# nrf-ethernet.net
KiCad netlist of a schematic drawn in EAGLE
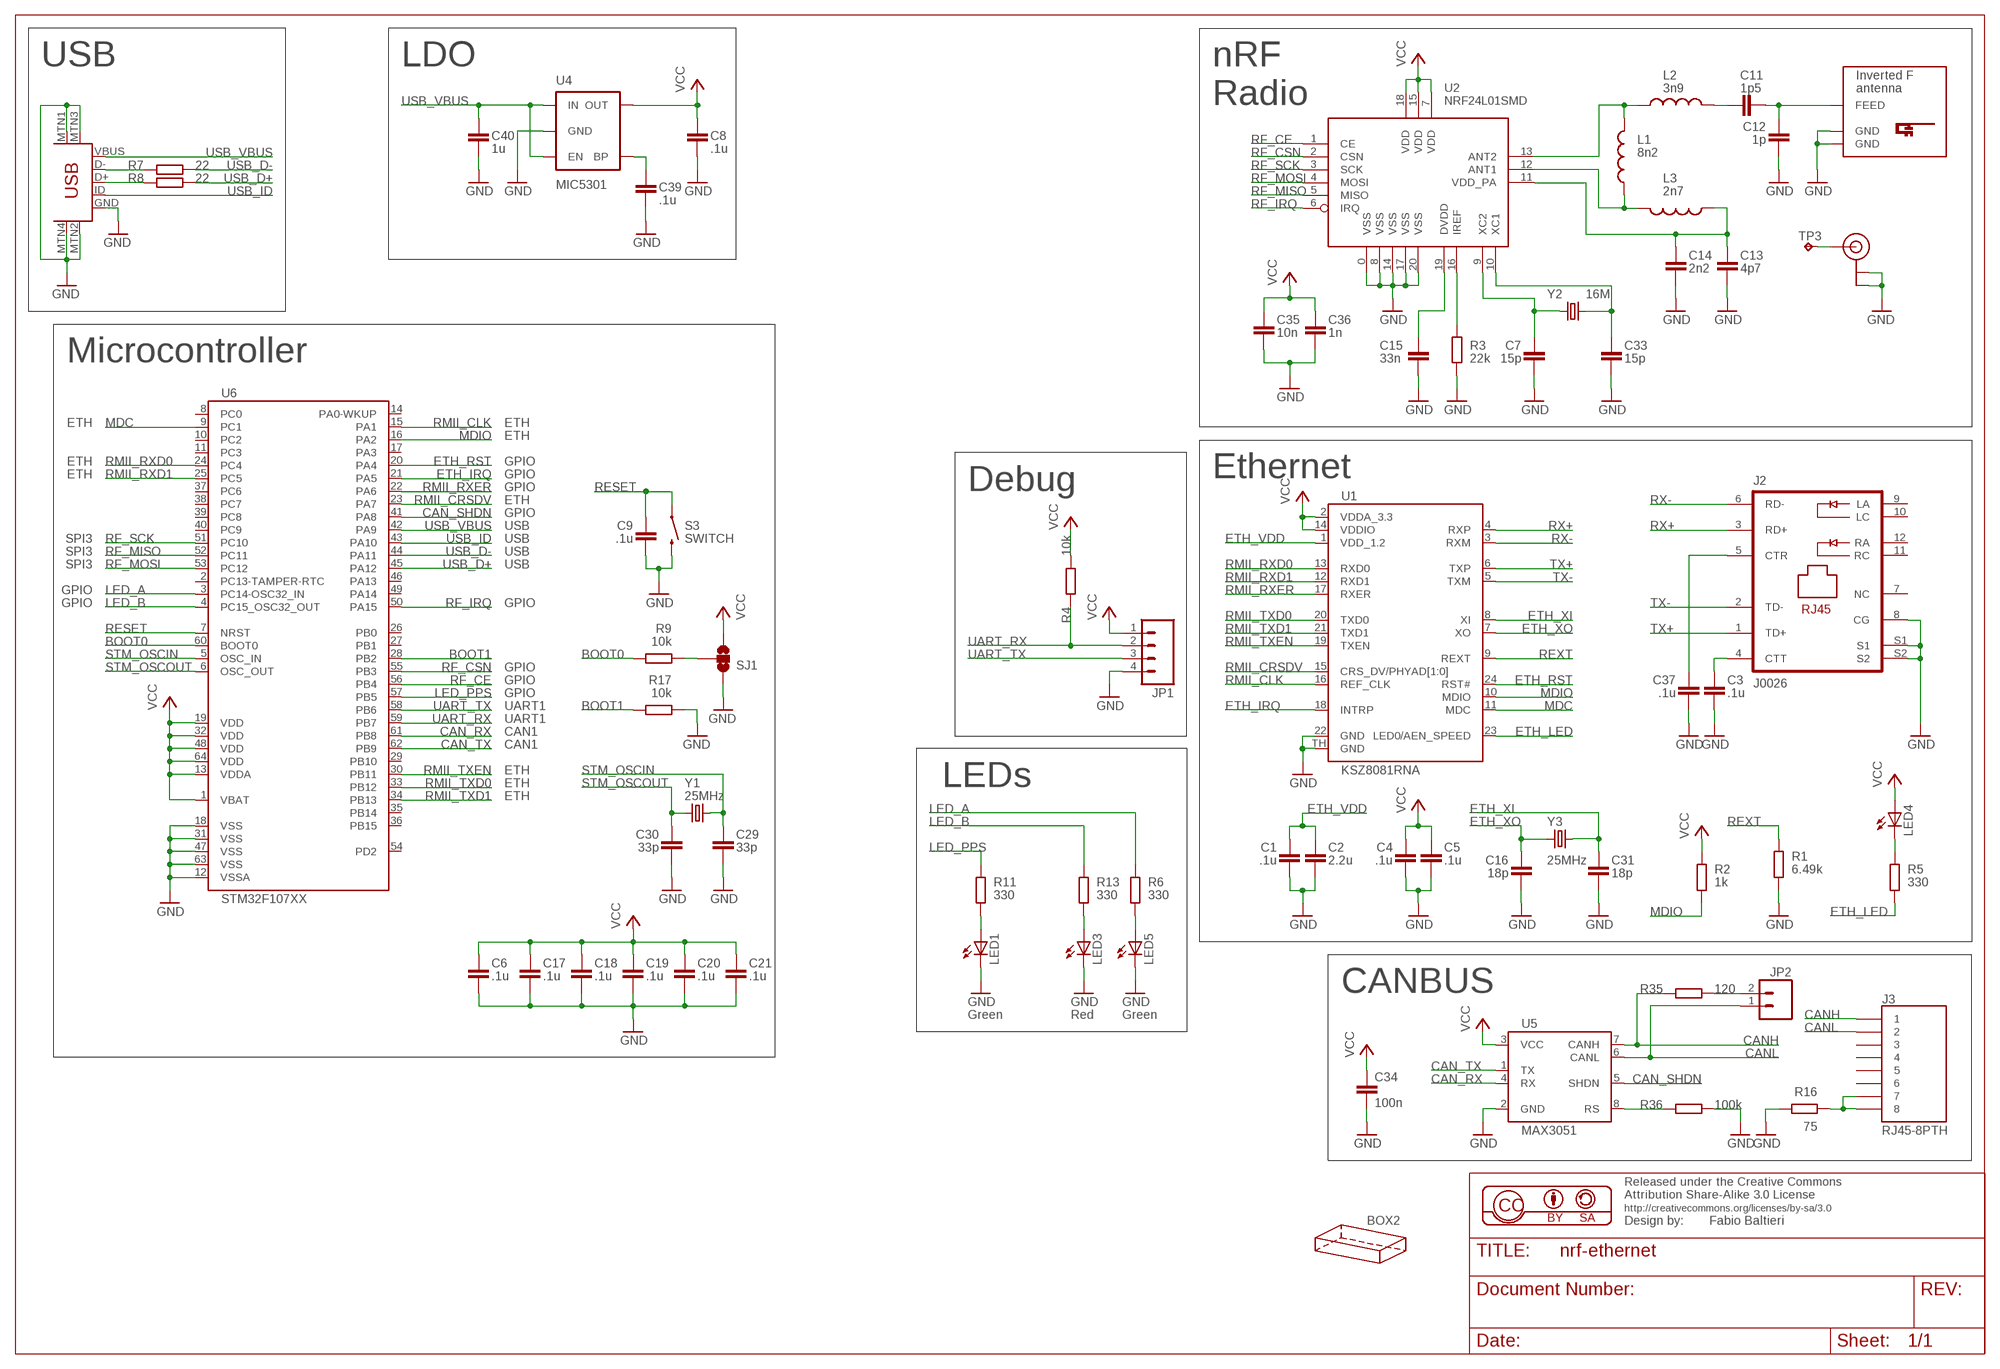
[diagram p0: schematic, sheet 1]

(export (version "E")
  (design (tool "Eeschema 10.0.6"))
  (components
    (comp (ref "BOX2")
      (value "HAMMOND-BOX-K")
      (footprint "eagle-import:1551K")
      (libsource (lib "eagle-import") (part "HAMMOND-BOX-K"))
    )
    (comp (ref "C1")
      (value ".1u")
      (footprint "eagle-import:C0603")
      (libsource (lib "eagle-import") (part "C-EUC0603"))
    )
    (comp (ref "C2")
      (value "2.2u")
      (footprint "eagle-import:C0603")
      (libsource (lib "eagle-import") (part "C-EUC0603"))
    )
    (comp (ref "C3")
      (value ".1u")
      (footprint "eagle-import:C0603")
      (libsource (lib "eagle-import") (part "C-EUC0603"))
    )
    (comp (ref "C4")
      (value ".1u")
      (footprint "eagle-import:C0603")
      (libsource (lib "eagle-import") (part "C-EUC0603"))
    )
    (comp (ref "C5")
      (value ".1u")
      (footprint "eagle-import:C0603")
      (libsource (lib "eagle-import") (part "C-EUC0603"))
    )
    (comp (ref "C6")
      (value ".1u")
      (footprint "eagle-import:C0603")
      (libsource (lib "eagle-import") (part "C-EUC0603"))
    )
    (comp (ref "C7")
      (value "15p")
      (footprint "eagle-import:C0603")
      (libsource (lib "eagle-import") (part "C-EUC0603"))
    )
    (comp (ref "C8")
      (value ".1u")
      (footprint "eagle-import:C0603")
      (libsource (lib "eagle-import") (part "C-EUC0603"))
    )
    (comp (ref "C9")
      (value ".1u")
      (footprint "eagle-import:C0603")
      (libsource (lib "eagle-import") (part "C-EUC0603"))
    )
    (comp (ref "C11")
      (value "1p5")
      (footprint "eagle-import:C0603")
      (libsource (lib "eagle-import") (part "C-EUC0603"))
    )
    (comp (ref "C12")
      (value "1p")
      (footprint "eagle-import:C0603")
      (libsource (lib "eagle-import") (part "C-EUC0603"))
    )
    (comp (ref "C13")
      (value "4p7")
      (footprint "eagle-import:C0603")
      (libsource (lib "eagle-import") (part "C-EUC0603"))
    )
    (comp (ref "C14")
      (value "2n2")
      (footprint "eagle-import:C0603")
      (libsource (lib "eagle-import") (part "C-EUC0603"))
    )
    (comp (ref "C15")
      (value "33n")
      (footprint "eagle-import:C0603")
      (libsource (lib "eagle-import") (part "C-EUC0603"))
    )
    (comp (ref "C16")
      (value "18p")
      (footprint "eagle-import:C0603")
      (libsource (lib "eagle-import") (part "C-EUC0603"))
    )
    (comp (ref "C17")
      (value ".1u")
      (footprint "eagle-import:C0603")
      (libsource (lib "eagle-import") (part "C-EUC0603"))
    )
    (comp (ref "C18")
      (value ".1u")
      (footprint "eagle-import:C0603")
      (libsource (lib "eagle-import") (part "C-EUC0603"))
    )
    (comp (ref "C19")
      (value ".1u")
      (footprint "eagle-import:C0603")
      (libsource (lib "eagle-import") (part "C-EUC0603"))
    )
    (comp (ref "C20")
      (value ".1u")
      (footprint "eagle-import:C0603")
      (libsource (lib "eagle-import") (part "C-EUC0603"))
    )
    (comp (ref "C21")
      (value ".1u")
      (footprint "eagle-import:C0603")
      (libsource (lib "eagle-import") (part "C-EUC0603"))
    )
    (comp (ref "C29")
      (value "33p")
      (footprint "eagle-import:C0603")
      (libsource (lib "eagle-import") (part "C-EUC0603"))
    )
    (comp (ref "C30")
      (value "33p")
      (footprint "eagle-import:C0603")
      (libsource (lib "eagle-import") (part "C-EUC0603"))
    )
    (comp (ref "C31")
      (value "18p")
      (footprint "eagle-import:C0603")
      (libsource (lib "eagle-import") (part "C-EUC0603"))
    )
    (comp (ref "C33")
      (value "15p")
      (footprint "eagle-import:C0603")
      (libsource (lib "eagle-import") (part "C-EUC0603"))
    )
    (comp (ref "C34")
      (value "100n")
      (footprint "eagle-import:C0603")
      (libsource (lib "eagle-import") (part "C-EUC0603"))
    )
    (comp (ref "C35")
      (value "10n")
      (footprint "eagle-import:C0603")
      (libsource (lib "eagle-import") (part "C-EUC0603"))
    )
    (comp (ref "C36")
      (value "1n")
      (footprint "eagle-import:C0603")
      (libsource (lib "eagle-import") (part "C-EUC0603"))
    )
    (comp (ref "C37")
      (value ".1u")
      (footprint "eagle-import:C0603")
      (libsource (lib "eagle-import") (part "C-EUC0603"))
    )
    (comp (ref "C39")
      (value ".1u")
      (footprint "eagle-import:C0603")
      (libsource (lib "eagle-import") (part "C-EUC0603"))
    )
    (comp (ref "C40")
      (value "1u")
      (footprint "eagle-import:C0603")
      (libsource (lib "eagle-import") (part "C-EUC0603"))
    )
    (comp (ref "J2")
      (value "J0026")
      (footprint "eagle-import:PJ-J0")
      (libsource (lib "eagle-import") (part "J0026"))
    )
    (comp (ref "J3")
      (value "RJ45-8PTH")
      (footprint "eagle-import:RJ45-8")
      (libsource (lib "eagle-import") (part "RJ45-8PTH"))
    )
    (comp (ref "JP1")
      (value "M04PTH")
      (footprint "eagle-import:1X04")
      (libsource (lib "eagle-import") (part "M04PTH"))
    )
    (comp (ref "JP2")
      (value "M02PTH")
      (footprint "eagle-import:1X02")
      (libsource (lib "eagle-import") (part "M02PTH"))
    )
    (comp (ref "L1")
      (value "8n2")
      (footprint "eagle-import:0603")
      (libsource (lib "eagle-import") (part "INDUCTOR0603"))
    )
    (comp (ref "L2")
      (value "3n9")
      (footprint "eagle-import:0603")
      (libsource (lib "eagle-import") (part "INDUCTOR0603"))
    )
    (comp (ref "L3")
      (value "2n7")
      (footprint "eagle-import:0603")
      (libsource (lib "eagle-import") (part "INDUCTOR0603"))
    )
    (comp (ref "LED1")
      (value "LEDCHIPLED_0805")
      (footprint "eagle-import:CHIPLED_0805")
      (libsource (lib "eagle-import") (part "LEDCHIPLED_0805"))
    )
    (comp (ref "LED3")
      (value "LEDCHIPLED_0805")
      (footprint "eagle-import:CHIPLED_0805")
      (libsource (lib "eagle-import") (part "LEDCHIPLED_0805"))
    )
    (comp (ref "LED4")
      (value "LEDCHIPLED_0805")
      (footprint "eagle-import:CHIPLED_0805")
      (libsource (lib "eagle-import") (part "LEDCHIPLED_0805"))
    )
    (comp (ref "LED5")
      (value "LEDCHIPLED_0805")
      (footprint "eagle-import:CHIPLED_0805")
      (libsource (lib "eagle-import") (part "LEDCHIPLED_0805"))
    )
    (comp (ref "R1")
      (value "6.49k")
      (footprint "eagle-import:R0603")
      (libsource (lib "eagle-import") (part "R-EU_R0603"))
    )
    (comp (ref "R2")
      (value "1k")
      (footprint "eagle-import:R0603")
      (libsource (lib "eagle-import") (part "R-EU_R0603"))
    )
    (comp (ref "R3")
      (value "22k")
      (footprint "eagle-import:R0603")
      (libsource (lib "eagle-import") (part "R-EU_R0603"))
    )
    (comp (ref "R4")
      (value "10k")
      (footprint "eagle-import:R0603")
      (libsource (lib "eagle-import") (part "R-EU_R0603"))
    )
    (comp (ref "R5")
      (value "330")
      (footprint "eagle-import:R0603")
      (libsource (lib "eagle-import") (part "R-EU_R0603"))
    )
    (comp (ref "R6")
      (value "330")
      (footprint "eagle-import:R0603")
      (libsource (lib "eagle-import") (part "R-EU_R0603"))
    )
    (comp (ref "R7")
      (value "22")
      (footprint "eagle-import:R0603")
      (libsource (lib "eagle-import") (part "R-EU_R0603"))
    )
    (comp (ref "R8")
      (value "22")
      (footprint "eagle-import:R0603")
      (libsource (lib "eagle-import") (part "R-EU_R0603"))
    )
    (comp (ref "R9")
      (value "10k")
      (footprint "eagle-import:R0603")
      (libsource (lib "eagle-import") (part "R-EU_R0603"))
    )
    (comp (ref "R11")
      (value "330")
      (footprint "eagle-import:R0603")
      (libsource (lib "eagle-import") (part "R-EU_R0603"))
    )
    (comp (ref "R13")
      (value "330")
      (footprint "eagle-import:R0603")
      (libsource (lib "eagle-import") (part "R-EU_R0603"))
    )
    (comp (ref "R16")
      (value "75")
      (footprint "eagle-import:R0805")
      (libsource (lib "eagle-import") (part "R-EU_R0805"))
    )
    (comp (ref "R17")
      (value "10k")
      (footprint "eagle-import:R0603")
      (libsource (lib "eagle-import") (part "R-EU_R0603"))
    )
    (comp (ref "R35")
      (value "120")
      (footprint "eagle-import:R0805")
      (libsource (lib "eagle-import") (part "R-EU_R0805"))
    )
    (comp (ref "R36")
      (value "100k")
      (footprint "eagle-import:R0603")
      (libsource (lib "eagle-import") (part "R-EU_R0603"))
    )
    (comp (ref "S3")
      (value "SWITCH")
      (footprint "eagle-import:TACTILE_SWITCH_SMD")
      (libsource (lib "eagle-import") (part "SWITCH-MOMENTARY-2SMD"))
    )
    (comp (ref "SJ1")
      (value "SOLDERJUMPER_2WAYS")
      (footprint "eagle-import:SJ_3")
      (libsource (lib "eagle-import") (part "SOLDERJUMPER_2WAYS"))
    )
    (comp (ref "TP3")
      (value "TPTP08SQ")
      (footprint "eagle-import:TP08SQ")
      (libsource (lib "eagle-import") (part "TPTP08SQ"))
    )
    (comp (ref "U$4")
      (value "USB-MINIB-5PIN")
      (footprint "eagle-import:USB-MINIB")
      (libsource (lib "eagle-import") (part "USB-MINIB-5PIN"))
    )
    (comp (ref "U$5")
      (value "INVERTED_F_ANTENNA-2")
      (footprint "eagle-import:DN007-2")
      (libsource (lib "eagle-import") (part "INVERTED_F_ANTENNA-2"))
    )
    (comp (ref "U$6")
      (value "U.FL")
      (footprint "eagle-import:U.FL")
      (libsource (lib "eagle-import") (part "U.FL"))
    )
    (comp (ref "U1")
      (value "KSZ8081RNA")
      (footprint "eagle-import:QFN24")
      (libsource (lib "eagle-import") (part "KSZ8081"))
    )
    (comp (ref "U2")
      (value "NRF24L01SMD")
      (footprint "eagle-import:QFN20")
      (libsource (lib "eagle-import") (part "NRF24L01SMD"))
    )
    (comp (ref "U4")
      (value "MIC5301")
      (footprint "eagle-import:SOT23-5")
      (libsource (lib "eagle-import") (part "V_REG_LDOSMD"))
    )
    (comp (ref "U5")
      (value "MAX3051")
      (footprint "eagle-import:SO08")
      (libsource (lib "eagle-import") (part "MAX3051"))
    )
    (comp (ref "U6")
      (value "STM32F107XX")
      (footprint "eagle-import:LQFP64")
      (libsource (lib "eagle-import") (part "STM32F107XX"))
    )
    (comp (ref "Y1")
      (value "25MHz")
      (footprint "eagle-import:CRYSTAL-SMD-5X3")
      (libsource (lib "eagle-import") (part "CRYSTAL5X3"))
    )
    (comp (ref "Y2")
      (value "16M")
      (footprint "eagle-import:CRYSTAL-SMD-5X3")
      (libsource (lib "eagle-import") (part "CRYSTAL5X3"))
    )
    (comp (ref "Y3")
      (value "25MHz")
      (footprint "eagle-import:CRYSTAL-SMD-5X3")
      (libsource (lib "eagle-import") (part "CRYSTAL5X3"))
    )
  )
  (nets
    (net (code "1") (name "/BOOT0") (class "Default")
      (node (ref "R9") (pin "2") (pinfunction "2_2") (pintype "passive"))
      (node (ref "U6") (pin "60") (pinfunction "BOOT0_60") (pintype "bidirectional"))
    )
    (net (code "2") (name "/BOOT1") (class "Default")
      (node (ref "R17") (pin "2") (pinfunction "2_2") (pintype "passive"))
      (node (ref "U6") (pin "28") (pinfunction "PB2_28") (pintype "bidirectional"))
    )
    (net (code "3") (name "/CANH") (class "Default")
      (node (ref "J3") (pin "1") (pinfunction "1_1") (pintype "bidirectional"))
      (node (ref "R35") (pin "1") (pinfunction "1_1") (pintype "passive"))
      (node (ref "U5") (pin "7") (pinfunction "CANH_7") (pintype "bidirectional"))
    )
    (net (code "4") (name "/CANL") (class "Default")
      (node (ref "J3") (pin "2") (pinfunction "2_2") (pintype "bidirectional"))
      (node (ref "JP2") (pin "1") (pinfunction "1_1") (pintype "passive"))
      (node (ref "U5") (pin "6") (pinfunction "CANL_6") (pintype "bidirectional"))
    )
    (net (code "5") (name "/CAN_RX") (class "Default")
      (node (ref "U5") (pin "4") (pinfunction "RX_4") (pintype "bidirectional"))
      (node (ref "U6") (pin "61") (pinfunction "PB8_61") (pintype "bidirectional"))
    )
    (net (code "6") (name "/CAN_SHDN") (class "Default")
      (node (ref "U5") (pin "5") (pinfunction "SHDN_5") (pintype "bidirectional"))
      (node (ref "U6") (pin "41") (pinfunction "PA8_41") (pintype "bidirectional"))
    )
    (net (code "7") (name "/CAN_TX") (class "Default")
      (node (ref "U5") (pin "1") (pinfunction "TX_1") (pintype "bidirectional"))
      (node (ref "U6") (pin "62") (pinfunction "PB9_62") (pintype "bidirectional"))
    )
    (net (code "8") (name "/ETH_IRQ") (class "Default")
      (node (ref "U1") (pin "18") (pinfunction "INTRP_18") (pintype "bidirectional"))
      (node (ref "U6") (pin "21") (pinfunction "PA5_21") (pintype "bidirectional"))
    )
    (net (code "9") (name "/ETH_LED") (class "Default")
      (node (ref "R5") (pin "1") (pinfunction "1_1") (pintype "passive"))
      (node (ref "U1") (pin "23") (pinfunction "LED0/AEN_SPEED_23") (pintype "bidirectional"))
    )
    (net (code "10") (name "/ETH_RST") (class "Default")
      (node (ref "U1") (pin "24") (pinfunction "RST#_24") (pintype "bidirectional"))
      (node (ref "U6") (pin "20") (pinfunction "PA4_20") (pintype "bidirectional"))
    )
    (net (code "11") (name "/ETH_VDD") (class "Default")
      (node (ref "C1") (pin "1") (pinfunction "1_1") (pintype "passive"))
      (node (ref "C2") (pin "1") (pinfunction "1_1") (pintype "passive"))
      (node (ref "U1") (pin "1") (pinfunction "VDD_1.2_1") (pintype "bidirectional"))
    )
    (net (code "12") (name "/ETH_XI") (class "Default")
      (node (ref "C31") (pin "1") (pinfunction "1_1") (pintype "passive"))
      (node (ref "U1") (pin "8") (pinfunction "XI_8") (pintype "bidirectional"))
      (node (ref "Y3") (pin "3") (pinfunction "2_3") (pintype "passive"))
    )
    (net (code "13") (name "/ETH_XO") (class "Default")
      (node (ref "C16") (pin "1") (pinfunction "1_1") (pintype "passive"))
      (node (ref "U1") (pin "7") (pinfunction "XO_7") (pintype "bidirectional"))
      (node (ref "Y3") (pin "1") (pinfunction "1_1") (pintype "passive"))
    )
    (net (code "14") (name "/LED_A") (class "Default")
      (node (ref "R6") (pin "2") (pinfunction "2_2") (pintype "passive"))
      (node (ref "U6") (pin "3") (pinfunction "PC14-OSC32_IN_3") (pintype "bidirectional"))
    )
    (net (code "15") (name "/LED_B") (class "Default")
      (node (ref "R13") (pin "2") (pinfunction "2_2") (pintype "passive"))
      (node (ref "U6") (pin "4") (pinfunction "PC15_OSC32_OUT_4") (pintype "bidirectional"))
    )
    (net (code "16") (name "/LED_PPS") (class "Default")
      (node (ref "R11") (pin "2") (pinfunction "2_2") (pintype "passive"))
      (node (ref "U6") (pin "57") (pinfunction "PB5_57") (pintype "bidirectional"))
    )
    (net (code "17") (name "/MDC") (class "Default")
      (node (ref "U1") (pin "11") (pinfunction "MDC_11") (pintype "bidirectional"))
      (node (ref "U6") (pin "9") (pinfunction "PC1_9") (pintype "bidirectional"))
    )
    (net (code "18") (name "/MDIO") (class "Default")
      (node (ref "R2") (pin "1") (pinfunction "1_1") (pintype "passive"))
      (node (ref "U1") (pin "10") (pinfunction "MDIO_10") (pintype "bidirectional"))
      (node (ref "U6") (pin "16") (pinfunction "PA2_16") (pintype "bidirectional"))
    )
    (net (code "19") (name "/RESET") (class "Default")
      (node (ref "C9") (pin "1") (pinfunction "1_1") (pintype "passive"))
      (node (ref "S3") (pin "1") (pinfunction "1_1") (pintype "passive"))
      (node (ref "U6") (pin "7") (pinfunction "NRST_7") (pintype "bidirectional"))
    )
    (net (code "20") (name "/REXT") (class "Default")
      (node (ref "R1") (pin "2") (pinfunction "2_2") (pintype "passive"))
      (node (ref "U1") (pin "9") (pinfunction "REXT_9") (pintype "bidirectional"))
    )
    (net (code "21") (name "/RF_CE") (class "Default")
      (node (ref "U2") (pin "1") (pinfunction "CE_1") (pintype "input"))
      (node (ref "U6") (pin "56") (pinfunction "PB4_56") (pintype "bidirectional"))
    )
    (net (code "22") (name "/RF_CSN") (class "Default")
      (node (ref "U2") (pin "2") (pinfunction "CSN_2") (pintype "input"))
      (node (ref "U6") (pin "55") (pinfunction "PB3_55") (pintype "bidirectional"))
    )
    (net (code "23") (name "/RF_IRQ") (class "Default")
      (node (ref "U2") (pin "6") (pinfunction "IRQ_6") (pintype "output"))
      (node (ref "U6") (pin "50") (pinfunction "PA15_50") (pintype "bidirectional"))
    )
    (net (code "24") (name "/RF_MISO") (class "Default")
      (node (ref "U2") (pin "5") (pinfunction "MISO_5") (pintype "output"))
      (node (ref "U6") (pin "52") (pinfunction "PC11_52") (pintype "bidirectional"))
    )
    (net (code "25") (name "/RF_MOSI") (class "Default")
      (node (ref "U2") (pin "4") (pinfunction "MOSI_4") (pintype "input"))
      (node (ref "U6") (pin "53") (pinfunction "PC12_53") (pintype "bidirectional"))
    )
    (net (code "26") (name "/RF_SCK") (class "Default")
      (node (ref "U2") (pin "3") (pinfunction "SCK_3") (pintype "input"))
      (node (ref "U6") (pin "51") (pinfunction "PC10_51") (pintype "bidirectional"))
    )
    (net (code "27") (name "/RMII_CLK") (class "Default")
      (node (ref "U1") (pin "16") (pinfunction "REF_CLK_16") (pintype "bidirectional"))
      (node (ref "U6") (pin "15") (pinfunction "PA1_15") (pintype "bidirectional"))
    )
    (net (code "28") (name "/RMII_CRSDV") (class "Default")
      (node (ref "U1") (pin "15") (pinfunction "CRS_DV/PHYAD[1:0]_15") (pintype "bidirectional"))
      (node (ref "U6") (pin "23") (pinfunction "PA7_23") (pintype "bidirectional"))
    )
    (net (code "29") (name "/RMII_RXD0") (class "Default")
      (node (ref "U1") (pin "13") (pinfunction "RXD0_13") (pintype "bidirectional"))
      (node (ref "U6") (pin "24") (pinfunction "PC4_24") (pintype "bidirectional"))
    )
    (net (code "30") (name "/RMII_RXD1") (class "Default")
      (node (ref "U1") (pin "12") (pinfunction "RXD1_12") (pintype "bidirectional"))
      (node (ref "U6") (pin "25") (pinfunction "PC5_25") (pintype "bidirectional"))
    )
    (net (code "31") (name "/RMII_RXER") (class "Default")
      (node (ref "U1") (pin "17") (pinfunction "RXER_17") (pintype "bidirectional"))
      (node (ref "U6") (pin "22") (pinfunction "PA6_22") (pintype "bidirectional"))
    )
    (net (code "32") (name "/RMII_TXD0") (class "Default")
      (node (ref "U1") (pin "20") (pinfunction "TXD0_20") (pintype "bidirectional"))
      (node (ref "U6") (pin "33") (pinfunction "PB12_33") (pintype "bidirectional"))
    )
    (net (code "33") (name "/RMII_TXD1") (class "Default")
      (node (ref "U1") (pin "21") (pinfunction "TXD1_21") (pintype "bidirectional"))
      (node (ref "U6") (pin "34") (pinfunction "PB13_34") (pintype "bidirectional"))
    )
    (net (code "34") (name "/RMII_TXEN") (class "Default")
      (node (ref "U1") (pin "19") (pinfunction "TXEN_19") (pintype "bidirectional"))
      (node (ref "U6") (pin "30") (pinfunction "PB11_30") (pintype "bidirectional"))
    )
    (net (code "35") (name "/RX+") (class "Default")
      (node (ref "J2") (pin "3") (pinfunction "RD+_3") (pintype "bidirectional"))
      (node (ref "U1") (pin "4") (pinfunction "RXP_4") (pintype "bidirectional"))
    )
    (net (code "36") (name "/RX-") (class "Default")
      (node (ref "J2") (pin "6") (pinfunction "RD-_6") (pintype "bidirectional"))
      (node (ref "U1") (pin "3") (pinfunction "RXM_3") (pintype "bidirectional"))
    )
    (net (code "37") (name "/STM_OSCIN") (class "Default")
      (node (ref "C29") (pin "1") (pinfunction "1_1") (pintype "passive"))
      (node (ref "U6") (pin "5") (pinfunction "OSC_IN_5") (pintype "bidirectional"))
      (node (ref "Y1") (pin "3") (pinfunction "2_3") (pintype "passive"))
    )
    (net (code "38") (name "/STM_OSCOUT") (class "Default")
      (node (ref "C30") (pin "1") (pinfunction "1_1") (pintype "passive"))
      (node (ref "U6") (pin "6") (pinfunction "OSC_OUT_6") (pintype "bidirectional"))
      (node (ref "Y1") (pin "1") (pinfunction "1_1") (pintype "passive"))
    )
    (net (code "39") (name "/TX+") (class "Default")
      (node (ref "J2") (pin "1") (pinfunction "TD+_1") (pintype "bidirectional"))
      (node (ref "U1") (pin "6") (pinfunction "TXP_6") (pintype "bidirectional"))
    )
    (net (code "40") (name "/TX-") (class "Default")
      (node (ref "J2") (pin "2") (pinfunction "TD-_2") (pintype "bidirectional"))
      (node (ref "U1") (pin "5") (pinfunction "TXM_5") (pintype "bidirectional"))
    )
    (net (code "41") (name "/UART_RX") (class "Default")
      (node (ref "JP1") (pin "2") (pinfunction "2_2") (pintype "passive"))
      (node (ref "R4") (pin "1") (pinfunction "1_1") (pintype "passive"))
      (node (ref "U6") (pin "59") (pinfunction "PB7_59") (pintype "bidirectional"))
    )
    (net (code "42") (name "/UART_TX") (class "Default")
      (node (ref "JP1") (pin "3") (pinfunction "3_3") (pintype "passive"))
      (node (ref "U6") (pin "58") (pinfunction "PB6_58") (pintype "bidirectional"))
    )
    (net (code "43") (name "/USB_D+") (class "Default")
      (node (ref "R8") (pin "2") (pinfunction "2_2") (pintype "passive"))
      (node (ref "U6") (pin "45") (pinfunction "PA12_45") (pintype "bidirectional"))
    )
    (net (code "44") (name "/USB_D-") (class "Default")
      (node (ref "R7") (pin "2") (pinfunction "2_2") (pintype "passive"))
      (node (ref "U6") (pin "44") (pinfunction "PA11_44") (pintype "bidirectional"))
    )
    (net (code "45") (name "/USB_ID") (class "Default")
      (node (ref "U$4") (pin "ID") (pinfunction "ID_ID") (pintype "bidirectional"))
      (node (ref "U6") (pin "43") (pinfunction "PA10_43") (pintype "bidirectional"))
    )
    (net (code "46") (name "/USB_VBUS") (class "Default")
      (node (ref "C40") (pin "1") (pinfunction "1_1") (pintype "passive"))
      (node (ref "U$4") (pin "VBUS") (pinfunction "VBUS_VBUS") (pintype "bidirectional"))
      (node (ref "U4") (pin "1") (pinfunction "IN_1") (pintype "input"))
      (node (ref "U4") (pin "3") (pinfunction "EN_3") (pintype "input"))
      (node (ref "U6") (pin "42") (pinfunction "PA9_42") (pintype "bidirectional"))
    )
    (net (code "47") (name "GND") (class "Default")
      (node (ref "C1") (pin "2") (pinfunction "2_2") (pintype "passive"))
      (node (ref "C12") (pin "2") (pinfunction "2_2") (pintype "passive"))
      (node (ref "C13") (pin "2") (pinfunction "2_2") (pintype "passive"))
      (node (ref "C14") (pin "2") (pinfunction "2_2") (pintype "passive"))
      (node (ref "C15") (pin "2") (pinfunction "2_2") (pintype "passive"))
      (node (ref "C16") (pin "2") (pinfunction "2_2") (pintype "passive"))
      (node (ref "C17") (pin "2") (pinfunction "2_2") (pintype "passive"))
      (node (ref "C18") (pin "2") (pinfunction "2_2") (pintype "passive"))
      (node (ref "C19") (pin "2") (pinfunction "2_2") (pintype "passive"))
      (node (ref "C2") (pin "2") (pinfunction "2_2") (pintype "passive"))
      (node (ref "C20") (pin "2") (pinfunction "2_2") (pintype "passive"))
      (node (ref "C21") (pin "2") (pinfunction "2_2") (pintype "passive"))
      (node (ref "C29") (pin "2") (pinfunction "2_2") (pintype "passive"))
      (node (ref "C3") (pin "2") (pinfunction "2_2") (pintype "passive"))
      (node (ref "C30") (pin "2") (pinfunction "2_2") (pintype "passive"))
      (node (ref "C31") (pin "2") (pinfunction "2_2") (pintype "passive"))
      (node (ref "C33") (pin "2") (pinfunction "2_2") (pintype "passive"))
      (node (ref "C34") (pin "2") (pinfunction "2_2") (pintype "passive"))
      (node (ref "C35") (pin "2") (pinfunction "2_2") (pintype "passive"))
      (node (ref "C36") (pin "2") (pinfunction "2_2") (pintype "passive"))
      (node (ref "C37") (pin "2") (pinfunction "2_2") (pintype "passive"))
      (node (ref "C39") (pin "2") (pinfunction "2_2") (pintype "passive"))
      (node (ref "C4") (pin "2") (pinfunction "2_2") (pintype "passive"))
      (node (ref "C40") (pin "2") (pinfunction "2_2") (pintype "passive"))
      (node (ref "C5") (pin "2") (pinfunction "2_2") (pintype "passive"))
      (node (ref "C6") (pin "2") (pinfunction "2_2") (pintype "passive"))
      (node (ref "C7") (pin "2") (pinfunction "2_2") (pintype "passive"))
      (node (ref "C8") (pin "2") (pinfunction "2_2") (pintype "passive"))
      (node (ref "C9") (pin "2") (pinfunction "2_2") (pintype "passive"))
      (node (ref "J2") (pin "8") (pinfunction "CG_8") (pintype "passive"))
      (node (ref "J2") (pin "S1") (pinfunction "S1_S1") (pintype "passive"))
      (node (ref "J2") (pin "S2") (pinfunction "S2_S2") (pintype "passive"))
      (node (ref "JP1") (pin "4") (pinfunction "4_4") (pintype "passive"))
      (node (ref "LED1") (pin "C") (pinfunction "C_C") (pintype "passive"))
      (node (ref "LED3") (pin "C") (pinfunction "C_C") (pintype "passive"))
      (node (ref "LED5") (pin "C") (pinfunction "C_C") (pintype "passive"))
      (node (ref "R1") (pin "1") (pinfunction "1_1") (pintype "passive"))
      (node (ref "R16") (pin "1") (pinfunction "1_1") (pintype "passive"))
      (node (ref "R17") (pin "1") (pinfunction "1_1") (pintype "passive"))
      (node (ref "R3") (pin "2") (pinfunction "2_2") (pintype "passive"))
      (node (ref "R36") (pin "2") (pinfunction "2_2") (pintype "passive"))
      (node (ref "S3") (pin "3") (pinfunction "2_3") (pintype "passive"))
      (node (ref "SJ1") (pin "1") (pinfunction "1_1") (pintype "passive"))
      (node (ref "U$4") (pin "GND") (pinfunction "GND_GND") (pintype "bidirectional"))
      (node (ref "U$4") (pin "MTN1") (pinfunction "MTN2_MTN1") (pintype "bidirectional"))
      (node (ref "U$4") (pin "MTN2") (pinfunction "MTN3_MTN2") (pintype "bidirectional"))
      (node (ref "U$4") (pin "MTN3") (pinfunction "MTN1_MTN3") (pintype "bidirectional"))
      (node (ref "U$4") (pin "MTN4") (pinfunction "MTN4_MTN4") (pintype "bidirectional"))
      (node (ref "U$5") (pin "GND") (pinfunction "GND_GND") (pintype "bidirectional"))
      (node (ref "U$5") (pin "GND@1") (pinfunction "GND_GND@1") (pintype "bidirectional"))
      (node (ref "U$6") (pin "P$1") (pinfunction "GND_P$1") (pintype "bidirectional"))
      (node (ref "U$6") (pin "P$2") (pinfunction "GND_P$2") (pintype "bidirectional"))
      (node (ref "U1") (pin "22") (pinfunction "GND_22") (pintype "bidirectional"))
      (node (ref "U1") (pin "TH") (pinfunction "GND_TH") (pintype "bidirectional"))
      (node (ref "U2") (pin "0") (pinfunction "VSS_0") (pintype "power_in"))
      (node (ref "U2") (pin "14") (pinfunction "VSS_14") (pintype "power_in"))
      (node (ref "U2") (pin "17") (pinfunction "VSS_17") (pintype "power_in"))
      (node (ref "U2") (pin "20") (pinfunction "VSS_20") (pintype "power_in"))
      (node (ref "U2") (pin "8") (pinfunction "VSS_8") (pintype "power_in"))
      (node (ref "U4") (pin "2") (pinfunction "GND_2") (pintype "input"))
      (node (ref "U5") (pin "2") (pinfunction "GND_2") (pintype "bidirectional"))
      (node (ref "U6") (pin "12") (pinfunction "VSSA_12") (pintype "bidirectional"))
      (node (ref "U6") (pin "18") (pinfunction "VSS_18") (pintype "bidirectional"))
      (node (ref "U6") (pin "31") (pinfunction "VSS_31") (pintype "bidirectional"))
      (node (ref "U6") (pin "47") (pinfunction "VSS_47") (pintype "bidirectional"))
      (node (ref "U6") (pin "63") (pinfunction "VSS_63") (pintype "bidirectional"))
    )
    (net (code "48") (name "Net-(C11-Pad1)") (class "Default")
      (node (ref "C11") (pin "1") (pinfunction "1_1") (pintype "passive"))
      (node (ref "L2") (pin "2") (pinfunction "2_2") (pintype "passive"))
    )
    (net (code "49") (name "Net-(C11-Pad2)") (class "Default")
      (node (ref "C11") (pin "2") (pinfunction "2_2") (pintype "passive"))
      (node (ref "C12") (pin "1") (pinfunction "1_1") (pintype "passive"))
      (node (ref "U$5") (pin "FEED") (pinfunction "FEED_FEED") (pintype "bidirectional"))
    )
    (net (code "50") (name "Net-(J2-CTR)") (class "Default")
      (node (ref "C37") (pin "1") (pinfunction "1_1") (pintype "passive"))
      (node (ref "J2") (pin "5") (pinfunction "CTR_5") (pintype "bidirectional"))
    )
    (net (code "51") (name "Net-(J2-CTT)") (class "Default")
      (node (ref "C3") (pin "1") (pinfunction "1_1") (pintype "passive"))
      (node (ref "J2") (pin "4") (pinfunction "CTT_4") (pintype "bidirectional"))
    )
    (net (code "52") (name "Net-(J3-Pad7)") (class "Default")
      (node (ref "J3") (pin "7") (pinfunction "7_7") (pintype "bidirectional"))
      (node (ref "J3") (pin "8") (pinfunction "8_8") (pintype "bidirectional"))
      (node (ref "R16") (pin "2") (pinfunction "2_2") (pintype "passive"))
    )
    (net (code "53") (name "Net-(JP2-Pad2)") (class "Default")
      (node (ref "JP2") (pin "2") (pinfunction "2_2") (pintype "passive"))
      (node (ref "R35") (pin "2") (pinfunction "2_2") (pintype "passive"))
    )
    (net (code "54") (name "Net-(LED1-PadA)") (class "Default")
      (node (ref "LED1") (pin "A") (pinfunction "A_A") (pintype "passive"))
      (node (ref "R11") (pin "1") (pinfunction "1_1") (pintype "passive"))
    )
    (net (code "55") (name "Net-(LED3-PadA)") (class "Default")
      (node (ref "LED3") (pin "A") (pinfunction "A_A") (pintype "passive"))
      (node (ref "R13") (pin "1") (pinfunction "1_1") (pintype "passive"))
    )
    (net (code "56") (name "Net-(LED4-PadC)") (class "Default")
      (node (ref "LED4") (pin "C") (pinfunction "C_C") (pintype "passive"))
      (node (ref "R5") (pin "2") (pinfunction "2_2") (pintype "passive"))
    )
    (net (code "57") (name "Net-(LED5-PadA)") (class "Default")
      (node (ref "LED5") (pin "A") (pinfunction "A_A") (pintype "passive"))
      (node (ref "R6") (pin "1") (pinfunction "1_1") (pintype "passive"))
    )
    (net (code "58") (name "Net-(R7-Pad1)") (class "Default")
      (node (ref "R7") (pin "1") (pinfunction "1_1") (pintype "passive"))
      (node (ref "U$4") (pin "D-") (pinfunction "D-_D-") (pintype "bidirectional"))
    )
    (net (code "59") (name "Net-(R8-Pad1)") (class "Default")
      (node (ref "R8") (pin "1") (pinfunction "1_1") (pintype "passive"))
      (node (ref "U$4") (pin "D+") (pinfunction "D+_D+") (pintype "bidirectional"))
    )
    (net (code "60") (name "Net-(R9-Pad1)") (class "Default")
      (node (ref "R9") (pin "1") (pinfunction "1_1") (pintype "passive"))
      (node (ref "SJ1") (pin "2") (pinfunction "2_2") (pintype "passive"))
    )
    (net (code "61") (name "Net-(U$6-SIGNAL)") (class "Default")
      (node (ref "TP3") (pin "TP") (pinfunction "TP_TP") (pintype "input"))
      (node (ref "U$6") (pin "P$3") (pinfunction "SIGNAL_P$3") (pintype "bidirectional"))
    )
    (net (code "62") (name "Net-(U2-ANT1)") (class "Default")
      (node (ref "L1") (pin "2") (pinfunction "2_2") (pintype "passive"))
      (node (ref "L3") (pin "2") (pinfunction "2_2") (pintype "passive"))
      (node (ref "U2") (pin "12") (pinfunction "ANT1_12") (pintype "output"))
    )
    (net (code "63") (name "Net-(U2-ANT2)") (class "Default")
      (node (ref "L1") (pin "1") (pinfunction "1_1") (pintype "passive"))
      (node (ref "L2") (pin "1") (pinfunction "1_1") (pintype "passive"))
      (node (ref "U2") (pin "13") (pinfunction "ANT2_13") (pintype "output"))
    )
    (net (code "64") (name "Net-(U2-DVDD)") (class "Default")
      (node (ref "C15") (pin "1") (pinfunction "1_1") (pintype "passive"))
      (node (ref "U2") (pin "19") (pinfunction "DVDD_19") (pintype "power_in"))
    )
    (net (code "65") (name "Net-(U2-IREF)") (class "Default")
      (node (ref "R3") (pin "1") (pinfunction "1_1") (pintype "passive"))
      (node (ref "U2") (pin "16") (pinfunction "IREF_16") (pintype "input"))
    )
    (net (code "66") (name "Net-(U2-VDD_PA)") (class "Default")
      (node (ref "C13") (pin "1") (pinfunction "1_1") (pintype "passive"))
      (node (ref "C14") (pin "1") (pinfunction "1_1") (pintype "passive"))
      (node (ref "L3") (pin "1") (pinfunction "1_1") (pintype "passive"))
      (node (ref "U2") (pin "11") (pinfunction "VDD_PA_11") (pintype "power_in"))
    )
    (net (code "67") (name "Net-(U2-XC1)") (class "Default")
      (node (ref "C33") (pin "1") (pinfunction "1_1") (pintype "passive"))
      (node (ref "U2") (pin "10") (pinfunction "XC1_10") (pintype "input"))
      (node (ref "Y2") (pin "3") (pinfunction "2_3") (pintype "passive"))
    )
    (net (code "68") (name "Net-(U2-XC2)") (class "Default")
      (node (ref "C7") (pin "1") (pinfunction "1_1") (pintype "passive"))
      (node (ref "U2") (pin "9") (pinfunction "XC2_9") (pintype "input"))
      (node (ref "Y2") (pin "1") (pinfunction "1_1") (pintype "passive"))
    )
    (net (code "69") (name "Net-(U4-BP)") (class "Default")
      (node (ref "C39") (pin "1") (pinfunction "1_1") (pintype "passive"))
      (node (ref "U4") (pin "4") (pinfunction "BP_4") (pintype "input"))
    )
    (net (code "70") (name "Net-(U5-RS)") (class "Default")
      (node (ref "R36") (pin "1") (pinfunction "1_1") (pintype "passive"))
      (node (ref "U5") (pin "8") (pinfunction "RS_8") (pintype "bidirectional"))
    )
    (net (code "71") (name "VCC") (class "Default")
      (node (ref "C17") (pin "1") (pinfunction "1_1") (pintype "passive"))
      (node (ref "C18") (pin "1") (pinfunction "1_1") (pintype "passive"))
      (node (ref "C19") (pin "1") (pinfunction "1_1") (pintype "passive"))
      (node (ref "C20") (pin "1") (pinfunction "1_1") (pintype "passive"))
      (node (ref "C21") (pin "1") (pinfunction "1_1") (pintype "passive"))
      (node (ref "C34") (pin "1") (pinfunction "1_1") (pintype "passive"))
      (node (ref "C35") (pin "1") (pinfunction "1_1") (pintype "passive"))
      (node (ref "C36") (pin "1") (pinfunction "1_1") (pintype "passive"))
      (node (ref "C4") (pin "1") (pinfunction "1_1") (pintype "passive"))
      (node (ref "C5") (pin "1") (pinfunction "1_1") (pintype "passive"))
      (node (ref "C6") (pin "1") (pinfunction "1_1") (pintype "passive"))
      (node (ref "C8") (pin "1") (pinfunction "1_1") (pintype "passive"))
      (node (ref "JP1") (pin "1") (pinfunction "1_1") (pintype "passive"))
      (node (ref "LED4") (pin "A") (pinfunction "A_A") (pintype "passive"))
      (node (ref "R2") (pin "2") (pinfunction "2_2") (pintype "passive"))
      (node (ref "R4") (pin "2") (pinfunction "2_2") (pintype "passive"))
      (node (ref "SJ1") (pin "3") (pinfunction "3_3") (pintype "passive"))
      (node (ref "U1") (pin "14") (pinfunction "VDDIO_14") (pintype "bidirectional"))
      (node (ref "U1") (pin "2") (pinfunction "VDDA_3.3_2") (pintype "bidirectional"))
      (node (ref "U2") (pin "15") (pinfunction "VDD_15") (pintype "power_in"))
      (node (ref "U2") (pin "18") (pinfunction "VDD_18") (pintype "power_in"))
      (node (ref "U2") (pin "7") (pinfunction "VDD_7") (pintype "power_in"))
      (node (ref "U4") (pin "5") (pinfunction "OUT_5") (pintype "passive"))
      (node (ref "U5") (pin "3") (pinfunction "VCC_3") (pintype "bidirectional"))
      (node (ref "U6") (pin "1") (pinfunction "VBAT_1") (pintype "bidirectional"))
      (node (ref "U6") (pin "13") (pinfunction "VDDA_13") (pintype "bidirectional"))
      (node (ref "U6") (pin "19") (pinfunction "VDD_19") (pintype "bidirectional"))
      (node (ref "U6") (pin "32") (pinfunction "VDD_32") (pintype "bidirectional"))
      (node (ref "U6") (pin "48") (pinfunction "VDD_48") (pintype "bidirectional"))
      (node (ref "U6") (pin "64") (pinfunction "VDD_64") (pintype "bidirectional"))
    )
    (net (code "72") (name "unconnected-(J2-LA-Pad9)") (class "Default")
      (node (ref "J2") (pin "9") (pinfunction "LA_9") (pintype "passive"))
    )
    (net (code "73") (name "unconnected-(J2-LC-Pad10)") (class "Default")
      (node (ref "J2") (pin "10") (pinfunction "LC_10") (pintype "passive"))
    )
    (net (code "74") (name "unconnected-(J2-NC-Pad7)") (class "Default")
      (node (ref "J2") (pin "7") (pinfunction "NC_7") (pintype "passive"))
    )
    (net (code "75") (name "unconnected-(J2-RA-Pad12)") (class "Default")
      (node (ref "J2") (pin "12") (pinfunction "RA_12") (pintype "passive"))
    )
    (net (code "76") (name "unconnected-(J2-RC-Pad11)") (class "Default")
      (node (ref "J2") (pin "11") (pinfunction "RC_11") (pintype "passive"))
    )
    (net (code "77") (name "unconnected-(J3-Pad3)") (class "Default")
      (node (ref "J3") (pin "3") (pinfunction "3_3") (pintype "bidirectional"))
    )
    (net (code "78") (name "unconnected-(J3-Pad4)") (class "Default")
      (node (ref "J3") (pin "4") (pinfunction "4_4") (pintype "bidirectional"))
    )
    (net (code "79") (name "unconnected-(J3-Pad5)") (class "Default")
      (node (ref "J3") (pin "5") (pinfunction "5_5") (pintype "bidirectional"))
    )
    (net (code "80") (name "unconnected-(J3-Pad6)") (class "Default")
      (node (ref "J3") (pin "6") (pinfunction "6_6") (pintype "bidirectional"))
    )
    (net (code "81") (name "unconnected-(U6-PA0-WKUP-Pad14)") (class "Default")
      (node (ref "U6") (pin "14") (pinfunction "PA0-WKUP_14") (pintype "bidirectional"))
    )
    (net (code "82") (name "unconnected-(U6-PA3-Pad17)") (class "Default")
      (node (ref "U6") (pin "17") (pinfunction "PA3_17") (pintype "bidirectional"))
    )
    (net (code "83") (name "unconnected-(U6-PA13-Pad46)") (class "Default")
      (node (ref "U6") (pin "46") (pinfunction "PA13_46") (pintype "bidirectional"))
    )
    (net (code "84") (name "unconnected-(U6-PA14-Pad49)") (class "Default")
      (node (ref "U6") (pin "49") (pinfunction "PA14_49") (pintype "bidirectional"))
    )
    (net (code "85") (name "unconnected-(U6-PB0-Pad26)") (class "Default")
      (node (ref "U6") (pin "26") (pinfunction "PB0_26") (pintype "bidirectional"))
    )
    (net (code "86") (name "unconnected-(U6-PB1-Pad27)") (class "Default")
      (node (ref "U6") (pin "27") (pinfunction "PB1_27") (pintype "bidirectional"))
    )
    (net (code "87") (name "unconnected-(U6-PB10-Pad29)") (class "Default")
      (node (ref "U6") (pin "29") (pinfunction "PB10_29") (pintype "bidirectional"))
    )
    (net (code "88") (name "unconnected-(U6-PB14-Pad35)") (class "Default")
      (node (ref "U6") (pin "35") (pinfunction "PB14_35") (pintype "bidirectional"))
    )
    (net (code "89") (name "unconnected-(U6-PB15-Pad36)") (class "Default")
      (node (ref "U6") (pin "36") (pinfunction "PB15_36") (pintype "bidirectional"))
    )
    (net (code "90") (name "unconnected-(U6-PC0-Pad8)") (class "Default")
      (node (ref "U6") (pin "8") (pinfunction "PC0_8") (pintype "bidirectional"))
    )
    (net (code "91") (name "unconnected-(U6-PC2-Pad10)") (class "Default")
      (node (ref "U6") (pin "10") (pinfunction "PC2_10") (pintype "bidirectional"))
    )
    (net (code "92") (name "unconnected-(U6-PC3-Pad11)") (class "Default")
      (node (ref "U6") (pin "11") (pinfunction "PC3_11") (pintype "bidirectional"))
    )
    (net (code "93") (name "unconnected-(U6-PC6-Pad37)") (class "Default")
      (node (ref "U6") (pin "37") (pinfunction "PC6_37") (pintype "bidirectional"))
    )
    (net (code "94") (name "unconnected-(U6-PC7-Pad38)") (class "Default")
      (node (ref "U6") (pin "38") (pinfunction "PC7_38") (pintype "bidirectional"))
    )
    (net (code "95") (name "unconnected-(U6-PC8-Pad39)") (class "Default")
      (node (ref "U6") (pin "39") (pinfunction "PC8_39") (pintype "bidirectional"))
    )
    (net (code "96") (name "unconnected-(U6-PC9-Pad40)") (class "Default")
      (node (ref "U6") (pin "40") (pinfunction "PC9_40") (pintype "bidirectional"))
    )
    (net (code "97") (name "unconnected-(U6-PC13-TAMPER-RTC-Pad2)") (class "Default")
      (node (ref "U6") (pin "2") (pinfunction "PC13-TAMPER-RTC_2") (pintype "bidirectional"))
    )
    (net (code "98") (name "unconnected-(U6-PD2-Pad54)") (class "Default")
      (node (ref "U6") (pin "54") (pinfunction "PD2_54") (pintype "bidirectional"))
    )
  )
)
